# SRD-05VDC-SL-c_Breakout.net
KiCad netlist of a schematic drawn in EAGLE
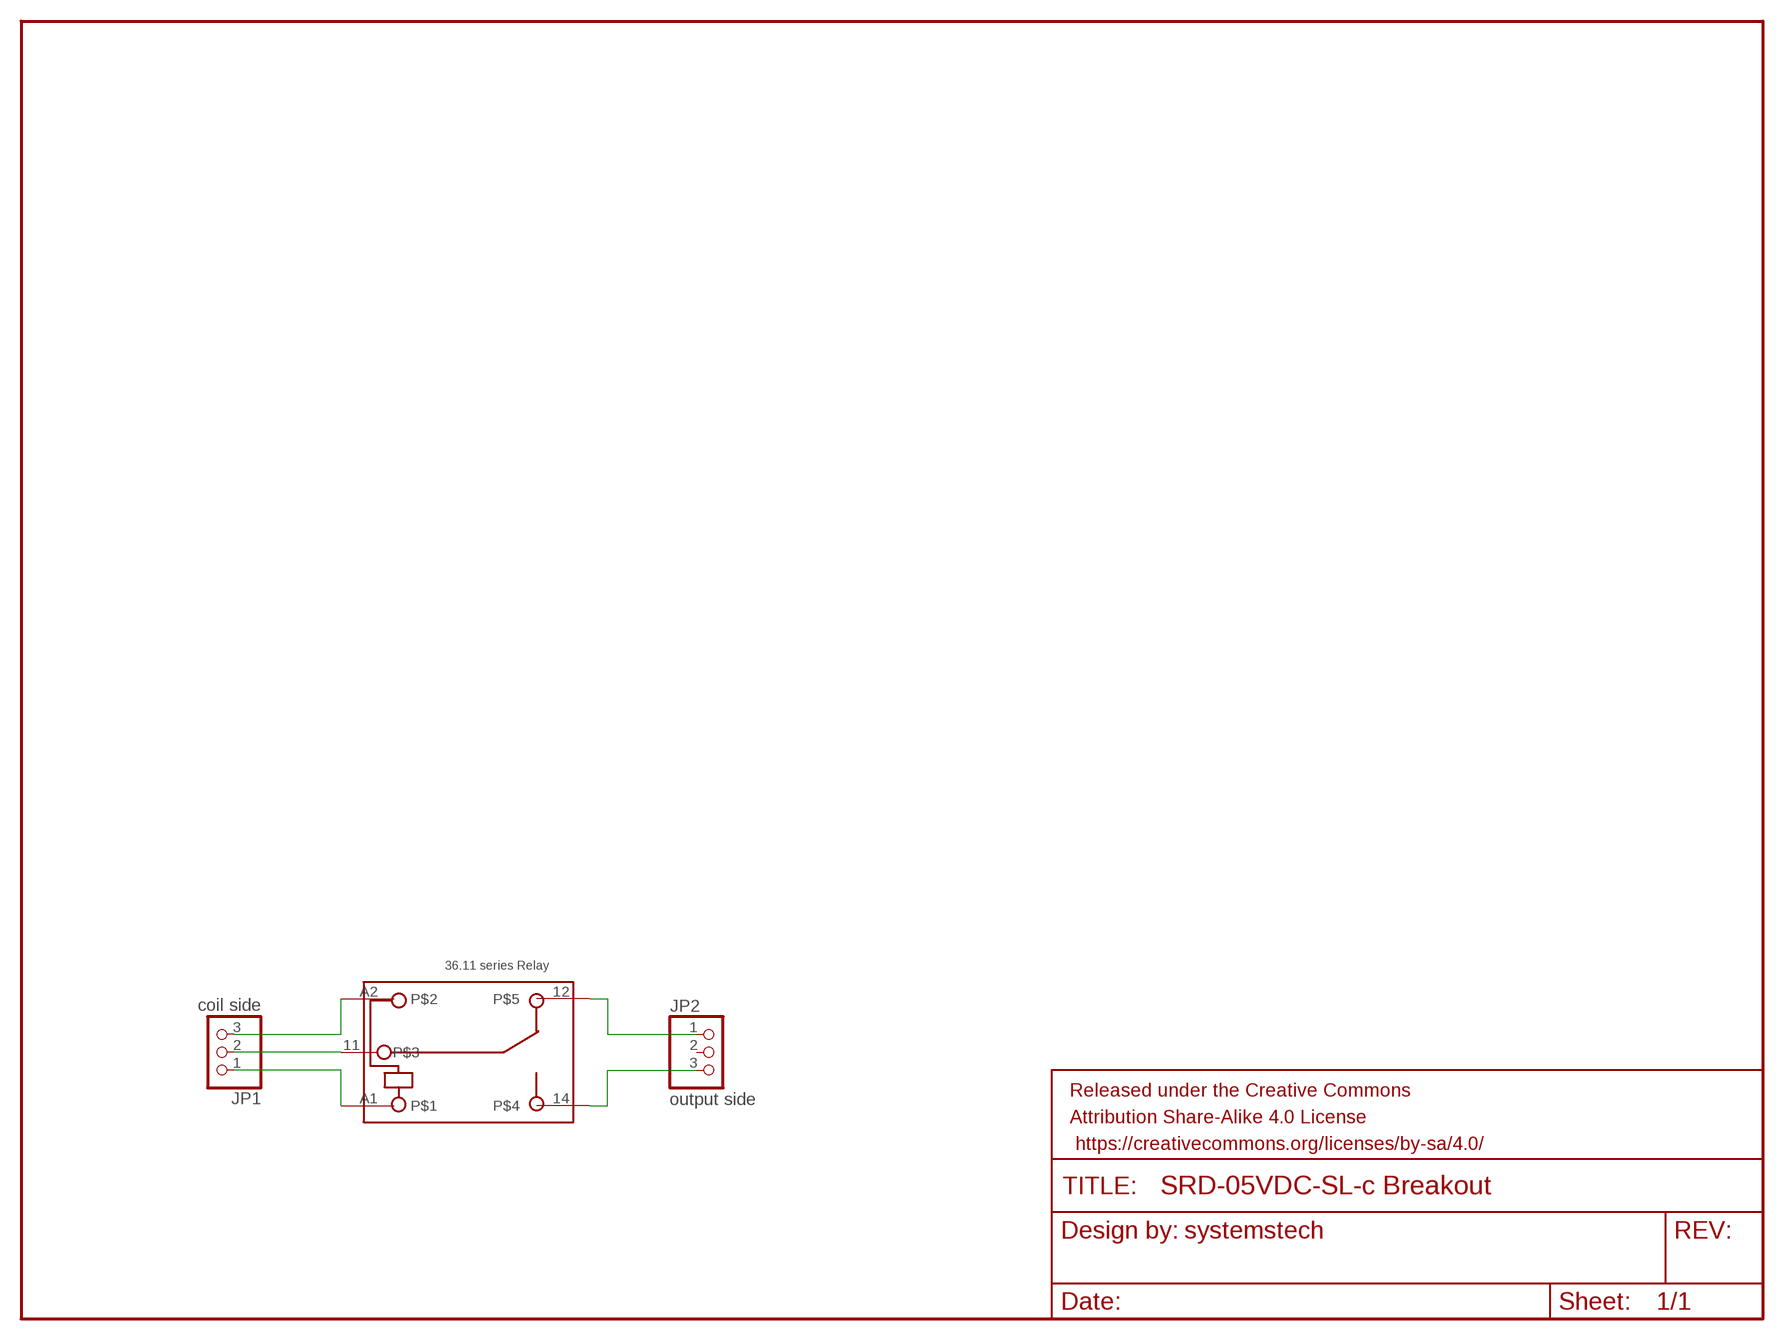
[diagram p0: schematic, sheet 1]

(export (version "E")
  (design (tool "Eeschema 10.0.6"))
  (components
    (comp (ref "FRAME1")
      (value "FRAME-LETTER")
      (footprint "eagle-import:CREATIVE_COMMONS")
      (libsource (lib "eagle-import") (part "FRAME-LETTER"))
    )
    (comp (ref "JP1")
      (value "coil side")
      (footprint "eagle-import:1X03")
      (libsource (lib "eagle-import") (part "PINHD-1X3"))
    )
    (comp (ref "JP2")
      (value "output side")
      (footprint "eagle-import:1X03")
      (libsource (lib "eagle-import") (part "PINHD-1X3"))
    )
    (comp (ref "K1")
      (value "36.11")
      (footprint "eagle-import:36.11")
      (libsource (lib "eagle-import") (part "36.11"))
    )
  )
  (nets
    (net (code "1") (name "Net-(K1-P$1)") (class "Default")
      (node (ref "JP1") (pin "1") (pinfunction "1_1") (pintype "passive"))
      (node (ref "K1") (pin "A1") (pinfunction "P$1_A1") (pintype "passive"))
    )
    (net (code "2") (name "Net-(K1-P$2)") (class "Default")
      (node (ref "JP1") (pin "3") (pinfunction "3_3") (pintype "passive"))
      (node (ref "K1") (pin "A2") (pinfunction "P$2_A2") (pintype "passive"))
    )
    (net (code "3") (name "Net-(K1-P$3)") (class "Default")
      (node (ref "JP1") (pin "2") (pinfunction "2_2") (pintype "passive"))
      (node (ref "K1") (pin "11") (pinfunction "P$3_11") (pintype "passive"))
    )
    (net (code "4") (name "Net-(K1-P$4)") (class "Default")
      (node (ref "JP2") (pin "3") (pinfunction "3_3") (pintype "passive"))
      (node (ref "K1") (pin "14") (pinfunction "P$4_14") (pintype "passive"))
    )
    (net (code "5") (name "Net-(K1-P$5)") (class "Default")
      (node (ref "JP2") (pin "1") (pinfunction "1_1") (pintype "passive"))
      (node (ref "K1") (pin "12") (pinfunction "P$5_12") (pintype "passive"))
    )
    (net (code "6") (name "unconnected-(JP2-Pad2)") (class "Default")
      (node (ref "JP2") (pin "2") (pinfunction "2_2") (pintype "passive"))
    )
  )
)
